# ControladorPOE.net
KiCad netlist of a schematic drawn in Altium Designer
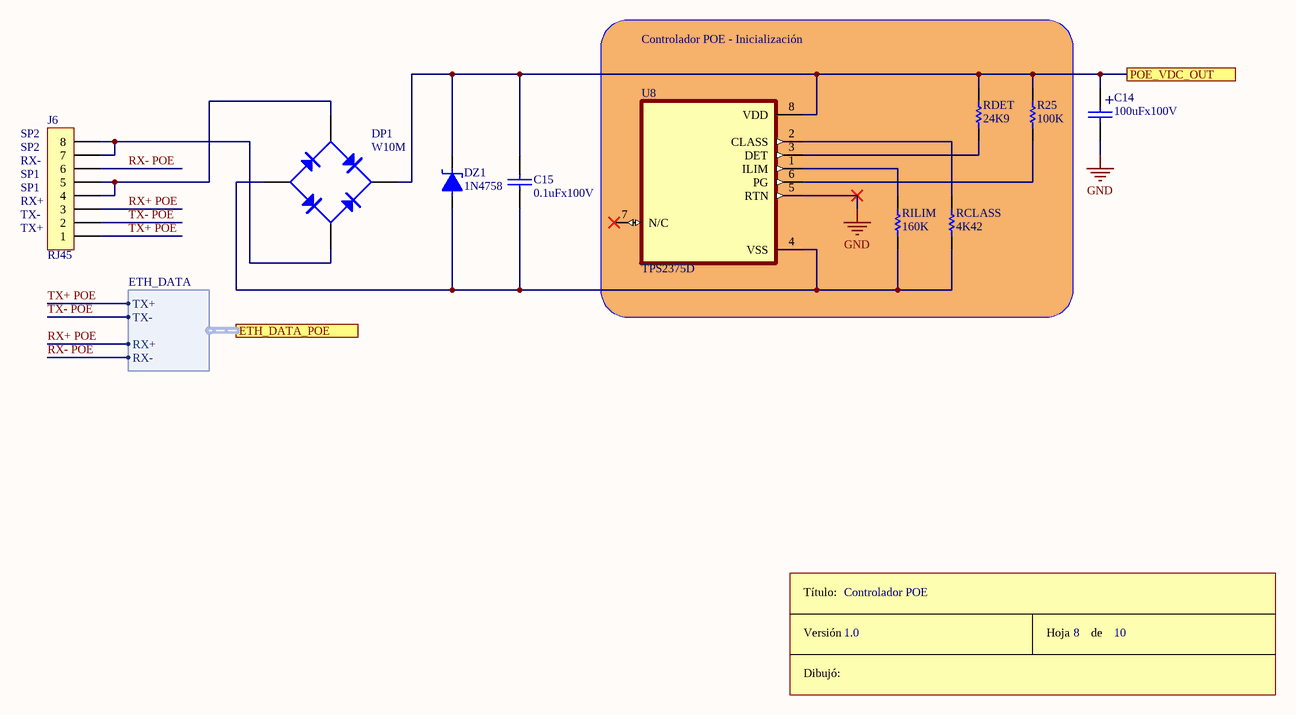
[diagram p0: ControladorPOE.SchDoc]

(export (version "E")
  (design (tool "Eeschema 10.0.6"))
  (components
    (comp (ref "C14") (value "100uFx100V") (footprint "CAP200RP") (libsource (lib "LIBEBAL") (part "CAPPOL")))
    (comp (ref "C15") (value "0.1uFx100V") (footprint "CAP200") (libsource (lib "LIBEBAL") (part "CAP")))
    (comp (ref "DP1") (value "W10M") (footprint "PUENTE - W10M") (libsource (lib "LIBEBAL") (part "PUENTE")))
    (comp (ref "DZ1") (value "1N4758") (footprint "DO41") (libsource (lib "LIBEBAL") (part "DIODO ZENER")))
    (comp (ref "J6") (value "RJ45") (footprint "RJ45") (libsource (lib "LIBEBAL") (part "RJ45")))
    (comp (ref "R25") (value "100K") (footprint "RES300") (libsource (lib "LIBEBAL") (part "RES")))
    (comp (ref "RCLASS") (value "4K42") (footprint "RES300") (libsource (lib "LIBEBAL") (part "RES")))
    (comp (ref "RDET") (value "24K9") (footprint "RES300") (libsource (lib "LIBEBAL") (part "RES")))
    (comp (ref "RILIM") (value "160K") (footprint "RES300") (libsource (lib "LIBEBAL") (part "RES")))
    (comp (ref "ROT7") (value "Rótulo") (libsource (lib "LIB PIO IX") (part "Rótulo")))
    (comp (ref "U8")
      (value "TPS2375D")
      (footprint "SOIC127P599X175-8N")
      (description "Class 3 PoE PD with latch protection 8-SOIC -40 to 85")
      (fields (field (name "DIGI-KEY_PART_NUMBER") "296-26922-2-ND") (field (name "MF") "Texas Instruments"))
      (libsource (lib "TPS2375D") (part "TPS2375D"))
    )
  )
  (nets
    (net (code "2") (name "/POE_VDC_OUT") (class "Default")
      (node (ref "C14") (pin "1") (pinfunction "1_1") (pintype "passive"))
      (node (ref "C15") (pin "1") (pinfunction "1_1") (pintype "passive"))
      (node (ref "DP1") (pin "1") (pinfunction "V+_1") (pintype "passive"))
      (node (ref "DZ1") (pin "2") (pinfunction "2_2") (pintype "passive"))
      (node (ref "R25") (pin "2") (pinfunction "2_2") (pintype "passive"))
      (node (ref "RDET") (pin "2") (pinfunction "2_2") (pintype "passive"))
      (node (ref "U8") (pin "8") (pinfunction "VDD_8") (pintype "power_in"))
    )
    (net (code "3") (name "/RX+ POE") (class "Default")
      (node (ref "J6") (pin "3") (pinfunction "3_3") (pintype "passive"))
    )
    (net (code "4") (name "/RX- POE") (class "Default")
      (node (ref "J6") (pin "6") (pinfunction "6_6") (pintype "passive"))
    )
    (net (code "5") (name "/TX+ POE") (class "Default")
      (node (ref "J6") (pin "1") (pinfunction "1_1") (pintype "passive"))
    )
    (net (code "6") (name "/TX- POE") (class "Default")
      (node (ref "J6") (pin "2") (pinfunction "2_2") (pintype "passive"))
    )
    (net (code "8") (name "GND") (class "Default")
      (node (ref "C14") (pin "2") (pinfunction "2_2") (pintype "passive"))
      (node (ref "U8") (pin "5") (pinfunction "RTN_5") (pintype "output"))
    )
    (net (code "9") (name "Net-(DP1-AC-Pad2)") (class "Default")
      (node (ref "DP1") (pin "2") (pinfunction "AC_2") (pintype "passive"))
      (node (ref "J6") (pin "4") (pinfunction "4_4") (pintype "passive"))
      (node (ref "J6") (pin "5") (pinfunction "5_5") (pintype "passive"))
    )
    (net (code "10") (name "Net-(DP1-AC-Pad4)") (class "Default")
      (node (ref "DP1") (pin "4") (pinfunction "AC_4") (pintype "passive"))
      (node (ref "J6") (pin "7") (pinfunction "7_7") (pintype "passive"))
      (node (ref "J6") (pin "8") (pinfunction "8_8") (pintype "passive"))
    )
    (net (code "11") (name "Net-(DP1-V-)") (class "Default")
      (node (ref "C15") (pin "2") (pinfunction "2_2") (pintype "passive"))
      (node (ref "DP1") (pin "3") (pinfunction "V-_3") (pintype "passive"))
      (node (ref "DZ1") (pin "1") (pinfunction "1_1") (pintype "passive"))
      (node (ref "RCLASS") (pin "1") (pinfunction "1_1") (pintype "passive"))
      (node (ref "RILIM") (pin "1") (pinfunction "1_1") (pintype "passive"))
      (node (ref "U8") (pin "4") (pinfunction "VSS_4") (pintype "power_in"))
    )
    (net (code "12") (name "Net-(U8-CLASS)") (class "Default")
      (node (ref "RCLASS") (pin "2") (pinfunction "2_2") (pintype "passive"))
      (node (ref "U8") (pin "2") (pinfunction "CLASS_2") (pintype "output"))
    )
    (net (code "13") (name "Net-(U8-DET)") (class "Default")
      (node (ref "RDET") (pin "1") (pinfunction "1_1") (pintype "passive"))
      (node (ref "U8") (pin "3") (pinfunction "DET_3") (pintype "output"))
    )
    (net (code "14") (name "Net-(U8-ILIM)") (class "Default")
      (node (ref "RILIM") (pin "2") (pinfunction "2_2") (pintype "passive"))
      (node (ref "U8") (pin "1") (pinfunction "ILIM_1") (pintype "output"))
    )
    (net (code "15") (name "Net-(U8-PG)") (class "Default")
      (node (ref "R25") (pin "1") (pinfunction "1_1") (pintype "passive"))
      (node (ref "U8") (pin "6") (pinfunction "PG_6") (pintype "output"))
    )
    (net (code "16") (name "unconnected-(U8-N{slash}C-Pad7)") (class "Default")
      (node (ref "U8") (pin "7") (pinfunction "N/C_7") (pintype "bidirectional+no_connect"))
    )
  )
)
